# Sheet1.net
KiCad netlist of a schematic drawn in Altium Designer
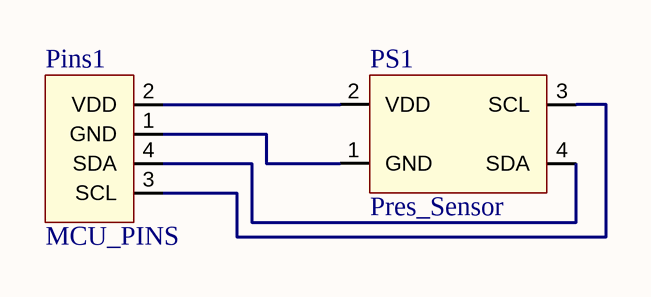
[diagram p0: Sheet1.SchDoc]

(export (version "E")
  (design (tool "Eeschema 10.0.6"))
  (components
    (comp (ref "Pins1")
      (value "MCU_PINS")
      (footprint "PIN_ROW")
      (libsource (lib "Pressure_sensor") (part "MCU_PINS"))
    )
    (comp (ref "PS1")
      (value "Pres_Sensor")
      (footprint "Pressure_Footprint")
      (libsource (lib "Pressure_sensor") (part "Pres_Sensor"))
    )
  )
  (nets
    (net (code "1") (name "Net-(PS1-GND)") (class "Default")
      (node (ref "PS1") (pin "1") (pinfunction "GND_1") (pintype "passive"))
      (node (ref "Pins1") (pin "1") (pinfunction "GND_1") (pintype "passive"))
    )
    (net (code "2") (name "Net-(PS1-SCL)") (class "Default")
      (node (ref "PS1") (pin "3") (pinfunction "SCL_3") (pintype "passive"))
      (node (ref "Pins1") (pin "3") (pinfunction "SCL_3") (pintype "passive"))
    )
    (net (code "3") (name "Net-(PS1-SDA)") (class "Default")
      (node (ref "PS1") (pin "4") (pinfunction "SDA_4") (pintype "passive"))
      (node (ref "Pins1") (pin "4") (pinfunction "SDA_4") (pintype "passive"))
    )
    (net (code "4") (name "Net-(PS1-VDD)") (class "Default")
      (node (ref "PS1") (pin "2") (pinfunction "VDD_2") (pintype "passive"))
      (node (ref "Pins1") (pin "2") (pinfunction "VDD_2") (pintype "passive"))
    )
  )
)
